# main.net
KiCad netlist of a schematic drawn in Altium Designer
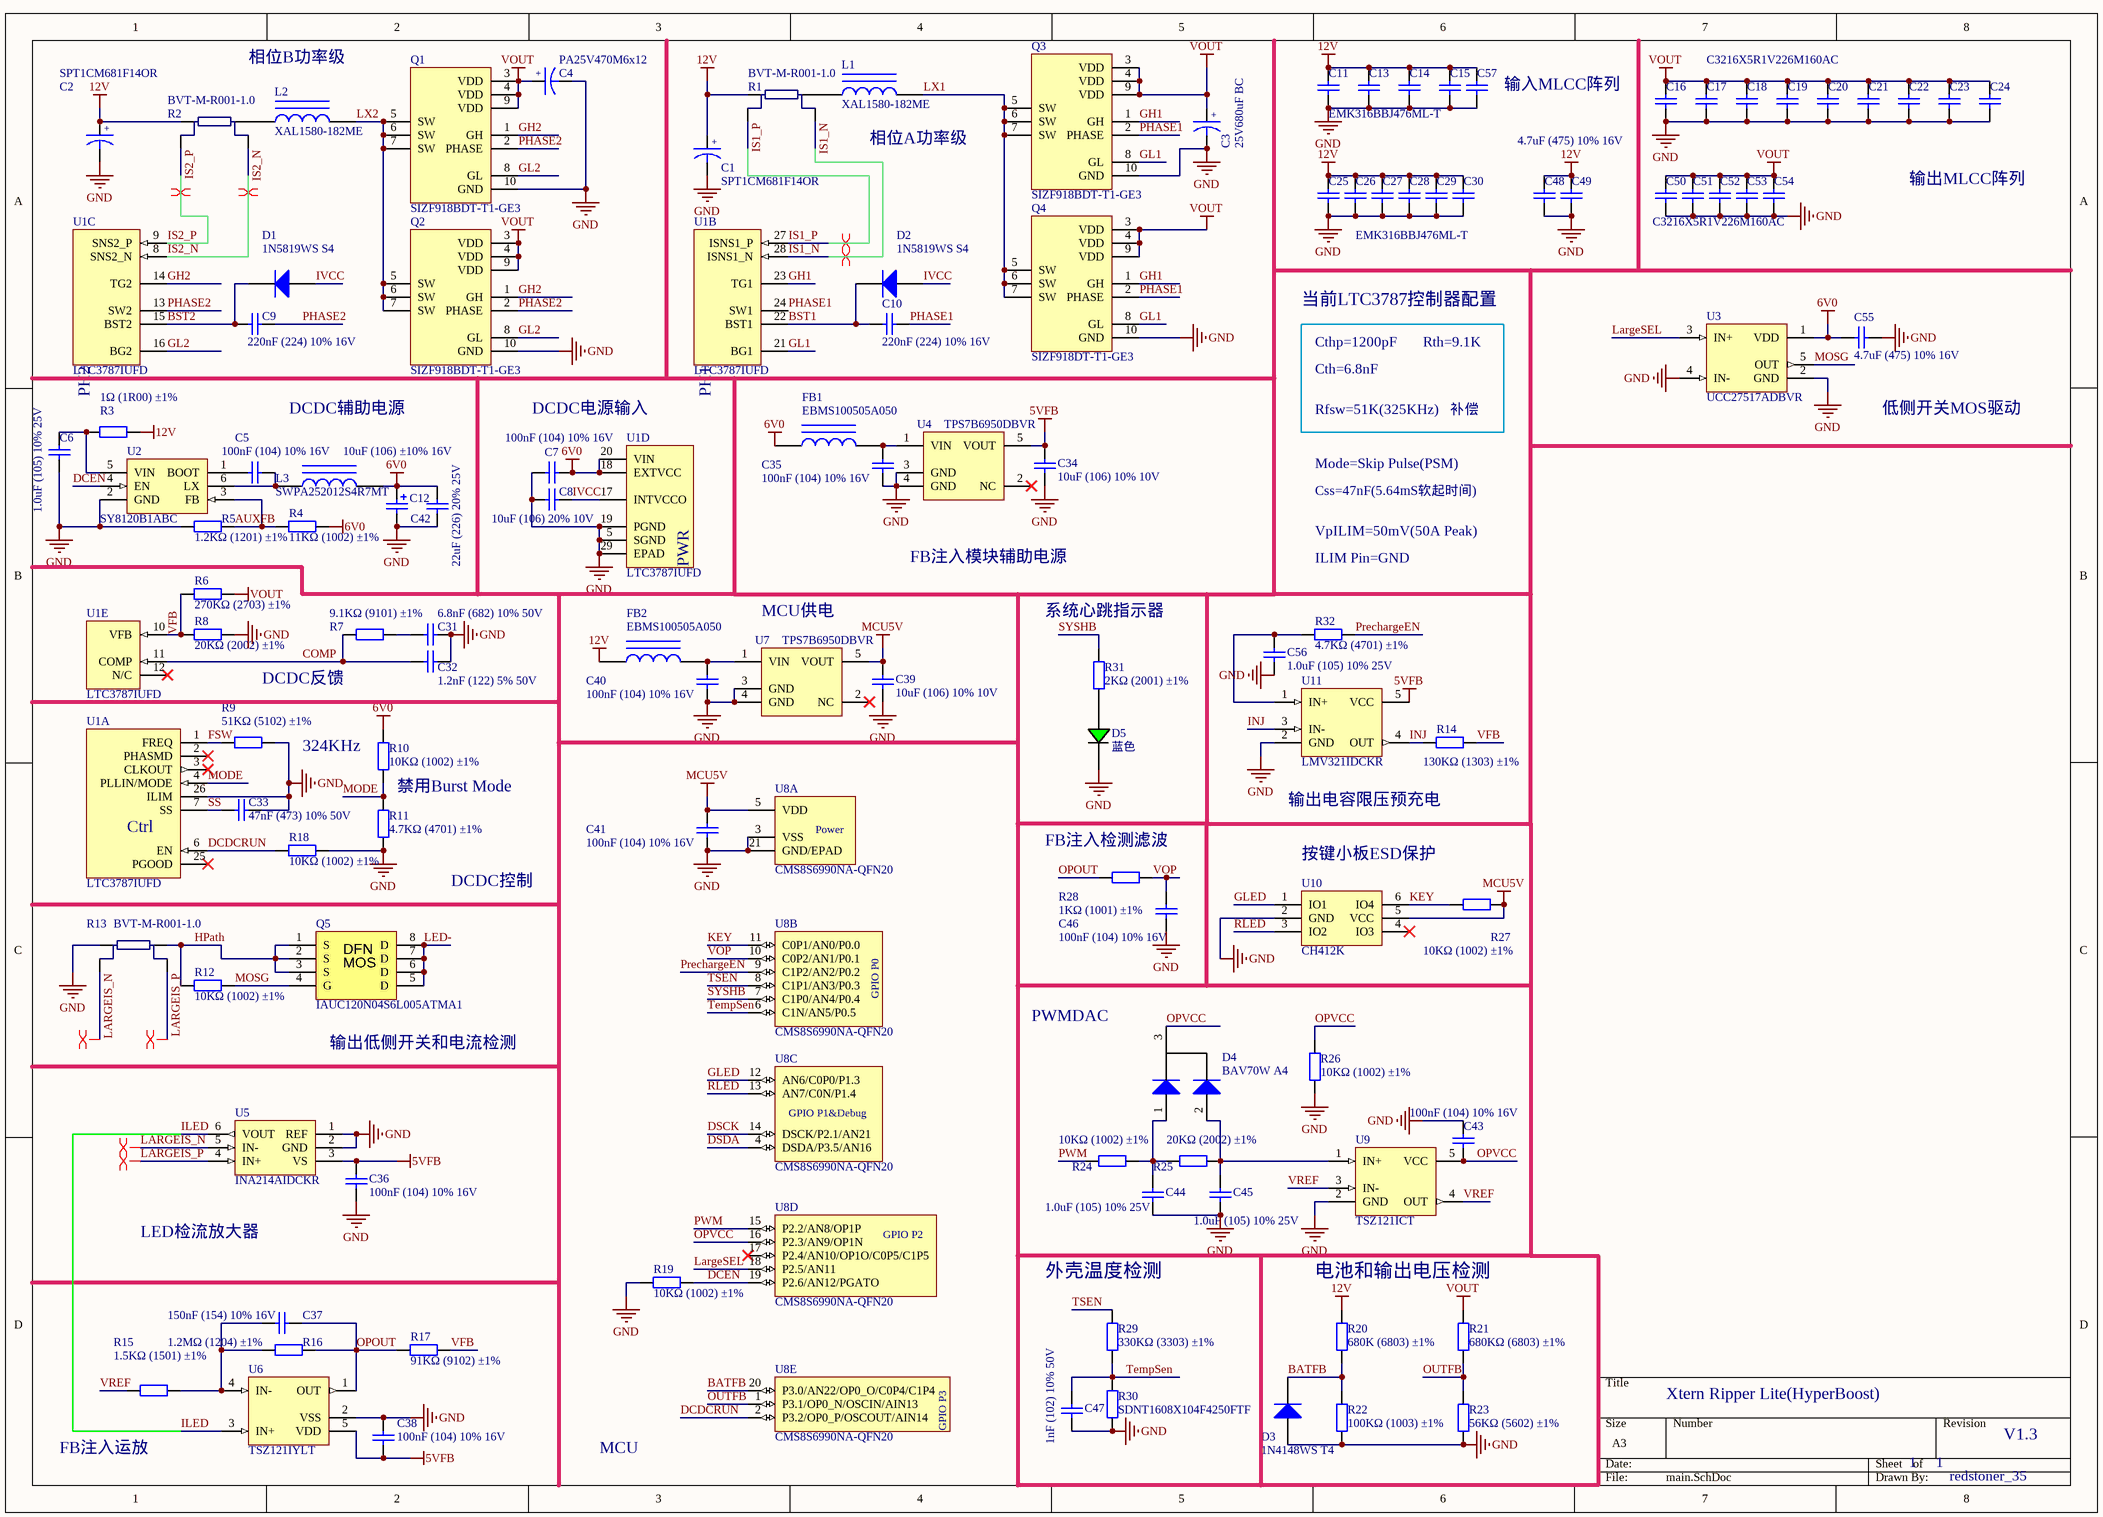
[diagram p0: main.SchDoc]

(export (version "E")
  (design (tool "Eeschema 10.0.6"))
  (components
    (comp (ref "C1")
      (value "SPT1CM681F14OR")
      (footprint "ElecCap_Hori")
      (description "直插固态电容，耐压16V容量680uF，尺寸6x11")
      (libsource (lib "山猫的集成库20190318") (part "CAP2"))
    )
    (comp (ref "C2")
      (value "SPT1CM681F14OR")
      (footprint "ElecCap_Hori")
      (description "直插固态电容，耐压16V容量680uF，尺寸6x11")
      (libsource (lib "山猫的集成库20190318") (part "CAP2"))
    )
    (comp (ref "C3")
      (value "25V680uF BC")
      (footprint "ElecCap_Hori")
      (description "绿宝石直插固态电容 680uF 25V BC系列，体积6x15")
      (libsource (lib "山猫的集成库20190318") (part "CAP2"))
    )
    (comp (ref "C4")
      (value "PA25V470M6x12")
      (footprint "ElecCap_Hori")
      (description "105°C 2000Hrs 直插固态电容。耐压25V容量470uF，尺寸D6.3mmxL12mm")
      (libsource (lib "山猫的集成库20190318") (part "CAP2"))
    )
    (comp (ref "C5")
      (value "100nF (104) 10% 16V")
      (footprint "0402_C")
      (description "贴片电容")
      (libsource (lib "Miscellaneous Devices LC") (part "0402 100nF (104) 10% 16V"))
    )
    (comp (ref "C6")
      (value "1.0uF (105) 10% 25V")
      (footprint "0402_C")
      (description "贴片电容")
      (libsource (lib "Miscellaneous Devices LC") (part "0402 1.0uF (105) 10% 25V"))
    )
    (comp (ref "C7")
      (value "100nF (104) 10% 16V")
      (footprint "0402_C")
      (description "贴片电容")
      (libsource (lib "Miscellaneous Devices LC") (part "0402 100nF (104) 10% 16V"))
    )
    (comp (ref "C8")
      (value "10uF (106) 20% 10V")
      (footprint "0402_C")
      (description "贴片电容")
      (libsource (lib "Miscellaneous Devices LC") (part "0402 10uF (106) 20% 6.3V"))
    )
    (comp (ref "C9")
      (value "220nF (224) 10% 16V")
      (footprint "0402_C")
      (description "贴片电容")
      (libsource (lib "Miscellaneous Devices LC") (part "0402 220nF (224) 10% 16V"))
    )
    (comp (ref "C10")
      (value "220nF (224) 10% 16V")
      (footprint "0402_C")
      (description "贴片电容")
      (libsource (lib "Miscellaneous Devices LC") (part "0402 220nF (224) 10% 16V"))
    )
    (comp (ref "C11")
      (value "EMK316BBJ476ML-T")
      (footprint "1206C")
      (description "1206尺寸太诱MLCC 16V 47uF X5R ±20%")
      (libsource (lib "山猫的集成库20190318") (part "Cap"))
    )
    (comp (ref "C12")
      (value "10uF (106) ±10% 16V")
      (footprint "CASE-A_3216")
      (description "钽电容")
      (libsource (lib "Miscellaneous Devices LC") (part "3216 10uF (106) 10% 16V"))
    )
    (comp (ref "C13")
      (value "EMK316BBJ476ML-T")
      (footprint "1206C")
      (description "1206尺寸太诱MLCC 16V 47uF X5R ±20%")
      (libsource (lib "山猫的集成库20190318") (part "Cap"))
    )
    (comp (ref "C14")
      (value "EMK316BBJ476ML-T")
      (footprint "1206C")
      (description "1206尺寸太诱MLCC 16V 47uF X5R ±20%")
      (libsource (lib "山猫的集成库20190318") (part "Cap"))
    )
    (comp (ref "C15")
      (value "EMK316BBJ476ML-T")
      (footprint "1206C")
      (description "1206尺寸太诱MLCC 16V 47uF X5R ±20%")
      (libsource (lib "山猫的集成库20190318") (part "Cap"))
    )
    (comp (ref "C16")
      (value "C3216X5R1V226M160AC")
      (footprint "1206C")
      (description "1206尺寸TDK MLCC 35V 22uF")
      (libsource (lib "山猫的集成库20190318") (part "Cap"))
    )
    (comp (ref "C17")
      (value "C3216X5R1V226M160AC")
      (footprint "1206C")
      (description "1206尺寸TDK MLCC 35V 22uF")
      (libsource (lib "山猫的集成库20190318") (part "Cap"))
    )
    (comp (ref "C18")
      (value "C3216X5R1V226M160AC")
      (footprint "1206C")
      (description "1206尺寸TDK MLCC 35V 22uF")
      (libsource (lib "山猫的集成库20190318") (part "Cap"))
    )
    (comp (ref "C19")
      (value "C3216X5R1V226M160AC")
      (footprint "1206C")
      (description "1206尺寸TDK MLCC 35V 22uF")
      (libsource (lib "山猫的集成库20190318") (part "Cap"))
    )
    (comp (ref "C20")
      (value "C3216X5R1V226M160AC")
      (footprint "1206C")
      (description "1206尺寸TDK MLCC 35V 22uF")
      (libsource (lib "山猫的集成库20190318") (part "Cap"))
    )
    (comp (ref "C21")
      (value "C3216X5R1V226M160AC")
      (footprint "1206C")
      (description "1206尺寸TDK MLCC 35V 22uF")
      (libsource (lib "山猫的集成库20190318") (part "Cap"))
    )
    (comp (ref "C22")
      (value "C3216X5R1V226M160AC")
      (footprint "1206C")
      (description "1206尺寸TDK MLCC 35V 22uF")
      (libsource (lib "山猫的集成库20190318") (part "Cap"))
    )
    (comp (ref "C23")
      (value "C3216X5R1V226M160AC")
      (footprint "1206C")
      (description "1206尺寸TDK MLCC 35V 22uF")
      (libsource (lib "山猫的集成库20190318") (part "Cap"))
    )
    (comp (ref "C24")
      (value "C3216X5R1V226M160AC")
      (footprint "1206C")
      (description "1206尺寸TDK MLCC 35V 22uF")
      (libsource (lib "山猫的集成库20190318") (part "Cap"))
    )
    (comp (ref "C25")
      (value "EMK316BBJ476ML-T")
      (footprint "1206C")
      (description "1206尺寸太诱MLCC 16V 47uF X5R ±20%")
      (libsource (lib "山猫的集成库20190318") (part "Cap"))
    )
    (comp (ref "C26")
      (value "EMK316BBJ476ML-T")
      (footprint "1206C")
      (description "1206尺寸太诱MLCC 16V 47uF X5R ±20%")
      (libsource (lib "山猫的集成库20190318") (part "Cap"))
    )
    (comp (ref "C27")
      (value "EMK316BBJ476ML-T")
      (footprint "1206C")
      (description "1206尺寸太诱MLCC 16V 47uF X5R ±20%")
      (libsource (lib "山猫的集成库20190318") (part "Cap"))
    )
    (comp (ref "C28")
      (value "EMK316BBJ476ML-T")
      (footprint "1206C")
      (description "1206尺寸太诱MLCC 16V 47uF X5R ±20%")
      (libsource (lib "山猫的集成库20190318") (part "Cap"))
    )
    (comp (ref "C29")
      (value "EMK316BBJ476ML-T")
      (footprint "1206C")
      (description "1206尺寸太诱MLCC 16V 47uF X5R ±20%")
      (libsource (lib "山猫的集成库20190318") (part "Cap"))
    )
    (comp (ref "C30")
      (value "EMK316BBJ476ML-T")
      (footprint "1206C")
      (description "1206尺寸太诱MLCC 16V 47uF X5R ±20%")
      (libsource (lib "山猫的集成库20190318") (part "Cap"))
    )
    (comp (ref "C31")
      (value "6.8nF (682) 10% 50V")
      (footprint "0402_C")
      (description "贴片电容")
      (libsource (lib "Miscellaneous Devices LC") (part "0402 6.8nF (682) 10% 50V"))
    )
    (comp (ref "C32")
      (value "1.2nF (122) 5% 50V")
      (footprint "0402_C")
      (description "贴片电容")
      (libsource (lib "Miscellaneous Devices LC") (part "0402 100pF (101) 5% 50V"))
    )
    (comp (ref "C33")
      (value "47nF (473) 10% 50V")
      (footprint "0402_C")
      (description "贴片电容")
      (libsource (lib "Miscellaneous Devices LC") (part "0402 100nF (104) 10% 16V"))
    )
    (comp (ref "C34")
      (value "10uF (106) 10% 10V")
      (footprint "0603_C")
      (description "贴片电容")
      (libsource (lib "Miscellaneous Devices LC") (part "0603 10uF (106) 10% 10V"))
    )
    (comp (ref "C35")
      (value "100nF (104) 10% 16V")
      (footprint "0402_C")
      (description "贴片电容")
      (libsource (lib "Miscellaneous Devices LC") (part "0402 100nF (104) 10% 16V"))
    )
    (comp (ref "C36")
      (value "100nF (104) 10% 16V")
      (footprint "0402_C")
      (description "贴片电容")
      (libsource (lib "Miscellaneous Devices LC") (part "0402 100nF (104) 10% 16V"))
    )
    (comp (ref "C37")
      (value "150nF (154) 10% 16V")
      (footprint "0402_C")
      (description "贴片电容")
      (libsource (lib "Miscellaneous Devices LC") (part "0402 100nF (104) 10% 16V"))
    )
    (comp (ref "C38")
      (value "100nF (104) 10% 16V")
      (footprint "0402_C")
      (description "贴片电容")
      (libsource (lib "Miscellaneous Devices LC") (part "0402 100nF (104) 10% 16V"))
    )
    (comp (ref "C39")
      (value "10uF (106) 10% 10V")
      (footprint "0603_C")
      (description "贴片电容")
      (libsource (lib "Miscellaneous Devices LC") (part "0603 10uF (106) 10% 10V"))
    )
    (comp (ref "C40")
      (value "100nF (104) 10% 16V")
      (footprint "0402_C")
      (description "贴片电容")
      (libsource (lib "Miscellaneous Devices LC") (part "0402 100nF (104) 10% 16V"))
    )
    (comp (ref "C41")
      (value "100nF (104) 10% 16V")
      (footprint "0402_C")
      (description "贴片电容")
      (libsource (lib "Miscellaneous Devices LC") (part "0402 100nF (104) 10% 16V"))
    )
    (comp (ref "C42")
      (value "22uF (226) 20% 25V")
      (footprint "0805_C")
      (description "贴片电容")
      (libsource (lib "Miscellaneous Devices LC") (part "0805 22uF (226) 20% 25V"))
    )
    (comp (ref "C43")
      (value "100nF (104) 10% 16V")
      (footprint "0402_C")
      (description "贴片电容")
      (libsource (lib "Miscellaneous Devices LC") (part "0402 100nF (104) 10% 16V"))
    )
    (comp (ref "C44")
      (value "1.0uF (105) 10% 25V")
      (footprint "0402_C")
      (description "贴片电容")
      (libsource (lib "Miscellaneous Devices LC") (part "0402 1.0uF (105) 10% 25V"))
    )
    (comp (ref "C45")
      (value "1.0uF (105) 10% 25V")
      (footprint "0402_C")
      (description "贴片电容")
      (libsource (lib "Miscellaneous Devices LC") (part "0402 1.0uF (105) 10% 25V"))
    )
    (comp (ref "C46")
      (value "100nF (104) 10% 16V")
      (footprint "0402_C")
      (description "贴片电容")
      (libsource (lib "Miscellaneous Devices LC") (part "0402 100nF (104) 10% 16V"))
    )
    (comp (ref "C47")
      (value "1nF (102) 10% 50V")
      (footprint "0402_C")
      (description "贴片电容")
      (libsource (lib "Miscellaneous Devices LC") (part "0402 1nF (102) 10% 50V"))
    )
    (comp (ref "C48")
      (value "4.7uF (475) 10% 16V")
      (footprint "0603_C")
      (description "贴片电容")
      (libsource (lib "Miscellaneous Devices LC") (part "0603 4.7uF (475) 10% 16V"))
    )
    (comp (ref "C49")
      (value "4.7uF (475) 10% 16V")
      (footprint "0603_C")
      (description "贴片电容")
      (libsource (lib "Miscellaneous Devices LC") (part "0603 4.7uF (475) 10% 16V"))
    )
    (comp (ref "C50")
      (value "C3216X5R1V226M160AC")
      (footprint "1206C")
      (description "1206尺寸TDK MLCC 35V 22uF")
      (libsource (lib "山猫的集成库20190318") (part "Cap"))
    )
    (comp (ref "C51")
      (value "C3216X5R1V226M160AC")
      (footprint "1206C")
      (description "1206尺寸TDK MLCC 35V 22uF")
      (libsource (lib "山猫的集成库20190318") (part "Cap"))
    )
    (comp (ref "C52")
      (value "C3216X5R1V226M160AC")
      (footprint "1206C")
      (description "1206尺寸TDK MLCC 35V 22uF")
      (libsource (lib "山猫的集成库20190318") (part "Cap"))
    )
    (comp (ref "C53")
      (value "C3216X5R1V226M160AC")
      (footprint "1206C")
      (description "1206尺寸TDK MLCC 35V 22uF")
      (libsource (lib "山猫的集成库20190318") (part "Cap"))
    )
    (comp (ref "C54")
      (value "C3216X5R1V226M160AC")
      (footprint "1206C")
      (description "1206尺寸TDK MLCC 35V 22uF")
      (libsource (lib "山猫的集成库20190318") (part "Cap"))
    )
    (comp (ref "C55")
      (value "4.7uF (475) 10% 16V")
      (footprint "0603_C")
      (description "贴片电容")
      (libsource (lib "Miscellaneous Devices LC") (part "0603 4.7uF (475) 10% 16V"))
    )
    (comp (ref "C56")
      (value "1.0uF (105) 10% 25V")
      (footprint "0402_C")
      (description "贴片电容")
      (libsource (lib "Miscellaneous Devices LC") (part "0402 1.0uF (105) 10% 25V"))
    )
    (comp (ref "C57")
      (value "EMK316BBJ476ML-T")
      (footprint "1206C")
      (description "1206尺寸太诱MLCC 16V 47uF X5R ±20%")
      (libsource (lib "山猫的集成库20190318") (part "Cap"))
    )
    (comp (ref "D1")
      (value "1N5819WS S4")
      (footprint "SOD-323")
      (description "二极管")
      (libsource (lib "Miscellaneous Devices LC") (part "SOD-323 1N4148WS T4"))
    )
    (comp (ref "D2")
      (value "1N5819WS S4")
      (footprint "SOD-323")
      (description "二极管")
      (libsource (lib "Miscellaneous Devices LC") (part "SOD-323 1N4148WS T4"))
    )
    (comp (ref "D3")
      (value "1N4148WS T4")
      (footprint "SOD-323")
      (description "二极管")
      (libsource (lib "Miscellaneous Devices LC") (part "SOD-323 1N4148WS T4"))
    )
    (comp (ref "D4")
      (value "BAV70W A4")
      (footprint "SC70-3")
      (description "开关二极管")
      (libsource (lib "Miscellaneous Devices LC") (part "SOT-23 BAV70 A4"))
    )
    (comp (ref "D5")
      (value "蓝色")
      (footprint "LED-0402")
      (description "0402(1005)贴片发光二极管")
      (libsource (lib "custom") (part "LED0402"))
    )
    (comp (ref "FB1")
      (value "EBMS100505A050")
      (footprint "0402_L")
      (description "贴片磁珠 200mA 5R±25% 100MHz")
      (libsource (lib "Miscellaneous Devices LC") (part "0402 12nH  5%"))
    )
    (comp (ref "FB2")
      (value "EBMS100505A050")
      (footprint "0402_L")
      (description "贴片磁珠 200mA 5R±25% 100MHz")
      (libsource (lib "Miscellaneous Devices LC") (part "0402 12nH  5%"))
    )
    (comp (ref "L1")
      (value "XAL1580-182ME")
      (footprint "XAL1580_xxxME")
      (description "线艺XAL系列电感")
      (libsource (lib "Miscellaneous Devices") (part "Inductor Iron"))
    )
    (comp (ref "L2")
      (value "XAL1580-182ME")
      (footprint "XAL1580_xxxME")
      (description "线艺XAL系列电感")
      (libsource (lib "Miscellaneous Devices") (part "Inductor Iron"))
    )
    (comp (ref "L3")
      (value "SWPA252012S4R7MT")
      (footprint "SWPA252010S")
      (description "线绕功率电感 2.5x2.0mm尺寸 1.2mm高度")
      (libsource (lib "") (part "Inductor Iron_1"))
    )
    (comp (ref "Q1")
      (value "SIZF918BDT-T1-GE3")
      (footprint "AOE6936")
      (description "30V Dual N-Channel 30 V (D-S) MOSFET With Schottky Diodes 3.6/1.5mΩ RdsON")
      (libsource (lib "custom") (part "AOE6936"))
    )
    (comp (ref "Q2")
      (value "SIZF918BDT-T1-GE3")
      (footprint "AOE6936")
      (description "30V Dual N-Channel 30 V (D-S) MOSFET With Schottky Diodes 3.6/1.5mΩ RdsON")
      (libsource (lib "custom") (part "AOE6936"))
    )
    (comp (ref "Q3")
      (value "SIZF918BDT-T1-GE3")
      (footprint "AOE6936")
      (description "30V Dual N-Channel 30 V (D-S) MOSFET With Schottky Diodes 3.6/1.5mΩ RdsON")
      (libsource (lib "custom") (part "AOE6936"))
    )
    (comp (ref "Q4")
      (value "SIZF918DT-T1-GE3")
      (footprint "AOE6936")
      (description "30V Dual N-Channel 30 V (D-S) MOSFET With Schottky Diodes 3.6/1.5mΩ RdsON")
      (libsource (lib "custom") (part "AOE6936"))
    )
    (comp (ref "Q5")
      (value "IAUC120N04S6L005ATMA1")
      (footprint "SON/DFN5x6(MOS)")
      (description "0.5mΩ 120A 40V OptiMOS 6 车规级MOSFET")
      (libsource (lib "custom") (part "SON/DFN5x6 MOS"))
    )
    (comp (ref "R1")
      (value "BVT-M-R001-1.0")
      (footprint "2512-Virtual4Wire")
      (description "德国伊萨精密检流电阻，2512 1mΩ±1% 锰铜材质 <50ppm/K P70℃=3W")
      (libsource (lib "custom") (part "shunt"))
    )
    (comp (ref "R2")
      (value "BVT-M-R001-1.0")
      (footprint "2512-Virtual4Wire")
      (description "德国伊萨精密检流电阻，2512 1mΩ±1% 锰铜材质 <50ppm/K P70℃=3W")
      (libsource (lib "custom") (part "shunt"))
    )
    (comp (ref "R3")
      (value "1Ω (1R00) ±1%")
      (footprint "0402_R")
      (description "贴片电阻")
      (libsource (lib "Miscellaneous Devices LC") (part "0402 1Ω (1R00) 1%"))
    )
    (comp (ref "R4")
      (value "11KΩ (1002) ±1%")
      (footprint "0402_R")
      (description "贴片电阻")
      (libsource (lib "") (part "0402 10KΩ (1002) 1%_2"))
    )
    (comp (ref "R5")
      (value "1.2KΩ (1201) ±1%")
      (footprint "0402_R")
      (description "贴片电阻")
      (libsource (lib "") (part "0402 10KΩ (1002) 1%_2"))
    )
    (comp (ref "R6")
      (value "270KΩ (2703) ±1%")
      (footprint "0402_R")
      (description "贴片电阻")
      (libsource (lib "") (part "0402 100KΩ (1003) 1%_1"))
    )
    (comp (ref "R7")
      (value "9.1KΩ (9101) ±1%")
      (footprint "0402_R")
      (description "贴片电阻")
      (libsource (lib "Miscellaneous Devices LC") (part "0402 10KΩ (1002) 1%"))
    )
    (comp (ref "R8")
      (value "20KΩ (2002) ±1%")
      (footprint "0402_R")
      (description "贴片电阻")
      (libsource (lib "Miscellaneous Devices LC") (part "0402 18KΩ (1802) 1%"))
    )
    (comp (ref "R9")
      (value "51KΩ (5102) ±1%")
      (footprint "0402_R")
      (description "贴片电阻")
      (libsource (lib "Miscellaneous Devices LC") (part "0402 56KΩ (5602) 1%"))
    )
    (comp (ref "R10")
      (value "10KΩ (1002) ±1%")
      (footprint "0402_R")
      (description "贴片电阻")
      (libsource (lib "") (part "0402 10KΩ (1002) 1%_1"))
    )
    (comp (ref "R11")
      (value "4.7KΩ (4701) ±1%")
      (footprint "0402_R")
      (description "贴片电阻")
      (libsource (lib "Miscellaneous Devices LC") (part "0402 4.7KΩ (4701) 1%"))
    )
    (comp (ref "R12")
      (value "10KΩ (1002) ±1%")
      (footprint "0402_R")
      (description "贴片电阻")
      (libsource (lib "") (part "0402 10KΩ (1002) 1%_2"))
    )
    (comp (ref "R13")
      (value "BVT-M-R001-1.0")
      (footprint "2512-Virtual4Wire")
      (description "德国伊萨精密检流电阻，2512 1mΩ±1% 锰铜材质 <50ppm/K P70℃=3W")
      (libsource (lib "custom") (part "shunt"))
    )
    (comp (ref "R14")
      (value "130KΩ (1303) ±1%")
      (footprint "0402_R")
      (description "贴片电阻")
      (libsource (lib "") (part "0402 100KΩ (1003) 1%_1"))
    )
    (comp (ref "R15")
      (value "1.5KΩ (1501) ±1%")
      (footprint "0402_R")
      (description "贴片电阻")
      (libsource (lib "Miscellaneous Devices LC") (part "0402 470Ω (4700) 1%"))
    )
    (comp (ref "R16")
      (value "1.2MΩ (1204) ±1%")
      (footprint "0402_R")
      (description "贴片电阻")
      (libsource (lib "Miscellaneous Devices LC") (part "0402 1MΩ (1004) 1%"))
    )
    (comp (ref "R17")
      (value "91KΩ (9102) ±1%")
      (footprint "0402_R")
      (description "贴片电阻")
      (libsource (lib "") (part "0402 100KΩ (1003) 1%_1"))
    )
    (comp (ref "R18")
      (value "10KΩ (1002) ±1%")
      (footprint "0402_R")
      (description "贴片电阻")
      (libsource (lib "Miscellaneous Devices LC") (part "0402 10KΩ (1002) 1%"))
    )
    (comp (ref "R19")
      (value "10KΩ (1002) ±1%")
      (footprint "0402_R")
      (description "贴片电阻")
      (libsource (lib "Miscellaneous Devices LC") (part "0402 10KΩ (1002) 1%"))
    )
    (comp (ref "R20")
      (value "680K (6803) ±1%")
      (footprint "0402_R")
      (description "贴片电阻")
      (libsource (lib "Miscellaneous Devices LC") (part "0402 680Ω (6800) 1%"))
    )
    (comp (ref "R21")
      (value "680KΩ (6803) ±1%")
      (footprint "0402_R")
      (description "贴片电阻")
      (libsource (lib "Miscellaneous Devices LC") (part "0402 470KΩ (4703) 1%"))
    )
    (comp (ref "R22")
      (value "100KΩ (1003) ±1%")
      (footprint "0402_R")
      (description "贴片电阻")
      (libsource (lib "Miscellaneous Devices LC") (part "0402 100KΩ (1003) 1%"))
    )
    (comp (ref "R23")
      (value "56KΩ (5602) ±1%")
      (footprint "0402_R")
      (description "贴片电阻")
      (libsource (lib "Miscellaneous Devices LC") (part "0402 100KΩ (1003) 1%"))
    )
    (comp (ref "R24")
      (value "10KΩ (1002) ±1%")
      (footprint "0402_R")
      (description "贴片电阻")
      (libsource (lib "Miscellaneous Devices LC") (part "0402 10KΩ (1002) 1%"))
    )
    (comp (ref "R25")
      (value "20KΩ (2002) ±1%")
      (footprint "0402_R")
      (description "贴片电阻")
      (libsource (lib "Miscellaneous Devices LC") (part "0402 20KΩ (2002) 1%"))
    )
    (comp (ref "R26")
      (value "10KΩ (1002) ±1%")
      (footprint "0402_R")
      (description "贴片电阻")
      (libsource (lib "") (part "0402 10KΩ (1002) 1%_1"))
    )
    (comp (ref "R27")
      (value "10KΩ (1002) ±1%")
      (footprint "0402_R")
      (description "贴片电阻")
      (libsource (lib "Miscellaneous Devices LC") (part "0402 10KΩ (1002) 1%"))
    )
    (comp (ref "R28")
      (value "1KΩ (1001) ±1%")
      (footprint "0402_R")
      (description "贴片电阻")
      (libsource (lib "Miscellaneous Devices LC") (part "0402 1KΩ (1001) 1%"))
    )
    (comp (ref "R29")
      (value "330KΩ (3303) ±1%")
      (footprint "0402_R")
      (description "贴片电阻")
      (libsource (lib "Miscellaneous Devices LC") (part "0402 330KΩ (3303) 1%"))
    )
    (comp (ref "R30")
      (value "SDNT1608X104F4250FTF")
      (footprint "0603_R")
      (description "0603贴片NTC热敏电阻，100KΩ (1003) ±1% B4250")
      (libsource (lib "Miscellaneous Devices LC") (part "0603 100KΩ (1003) 1%"))
    )
    (comp (ref "R31")
      (value "2KΩ (2001) ±1%")
      (footprint "0402_R")
      (description "贴片电阻")
      (libsource (lib "Miscellaneous Devices LC") (part "0402 2KΩ (2001) 1%"))
    )
    (comp (ref "R32")
      (value "4.7KΩ (4701) ±1%")
      (footprint "0402_R")
      (description "贴片电阻")
      (libsource (lib "Miscellaneous Devices LC") (part "0402 20KΩ (2002) 1%"))
    )
    (comp (ref "U1")
      (value "LTC3787IUFD")
      (footprint "UFD-QFN28")
      (description "PolyPhase Synchronous Boost Controller for 2 Phases")
      (libsource (lib "custom") (part "LTC3787IUFD"))
    )
    (comp (ref "U2")
      (value "SY8120B1ABC")
      (footprint "SOT95P245X110-6N")
      (description "2A输出电流，18V耐压同步降压转换器，SOT-23-6封装")
      (libsource (lib "custom") (part "SY8120"))
    )
    (comp (ref "U3")
      (value "UCC27517ADBVR")
      (footprint "SOT95P245X110-5N")
      (description "4A Gate Driver SOT-23 Low side")
      (libsource (lib "custom") (part "UCC27517ADBVR"))
    )
    (comp (ref "U4")
      (value "TPS7B6950DBVR")
      (footprint "SOT95P245X110-5N")
      (description "150mA 40V max input Ultra low Iq LDO,fixed 5V output")
      (libsource (lib "custom") (part "TPS7B6933DBVR"))
    )
    (comp (ref "U5")
      (value "INA214AIDCKR")
      (footprint "SC70-6")
      (description "100V/V增益 26V最高共模电压，高低测通用双向高精度检流放大器 SC70-6封装")
      (libsource (lib "custom") (part "INA199A2DCKR"))
    )
    (comp (ref "U6")
      (value "TSZ121IYLT")
      (footprint "SOT95P245X110-5N")
      (description "高精度零漂移低功耗5V运放 400Khz GBW SOT23-5封装")
      (libsource (lib "custom") (part "TLV333IDBVR"))
    )
    (comp (ref "U7")
      (value "TPS7B6950DBVR")
      (footprint "SOT95P245X110-5N")
      (description "150mA 40V max input Ultra low Iq LDO,fixed 5V output")
      (libsource (lib "custom") (part "TPS7B6933DBVR"))
    )
    (comp (ref "U8")
      (value "CMS8S6990NA-QFN20")
      (footprint "QFN40P300X300X800_HS-21N")
      (description "增强型闪存1T 8051单片机，16KB Flash 256+1K XRAM")
      (libsource (lib "custom") (part "CM8S6990NA-QFN20"))
    )
    (comp (ref "U9")
      (value "TSZ121ICT")
      (footprint "SC70-5")
      (description "高精度零漂移低功耗5V运放 400Khz GBW SC70-5封装")
      (libsource (lib "custom") (part "LMV321IDCKR"))
    )
    (comp (ref "U10")
      (value "CH412K")
      (footprint "SC70-6")
      (description "very low capacity quad IO ESD protection Array")
      (libsource (lib "custom") (part "CH412K"))
    )
    (comp (ref "U11")
      (value "LMV321IDCKR")
      (footprint "SC70-5")
      (description "CMOS超小型运算放大器，SC70-5")
      (libsource (lib "custom") (part "LMV321IDCKR"))
    )
  )
  (nets
    (net (code "1") (name "/AUXFB") (class "Default")
      (node (ref "R4") (pin "2") (pinfunction "2_2") (pintype "passive"))
      (node (ref "R5") (pin "1") (pinfunction "1_1") (pintype "passive"))
      (node (ref "U2") (pin "3") (pinfunction "FB_3") (pintype "input"))
    )
    (net (code "2") (name "/BATFB") (class "Default")
      (node (ref "D3") (pin "2") (pinfunction "K_2") (pintype "passive"))
      (node (ref "R20") (pin "1") (pinfunction "1_1") (pintype "passive"))
      (node (ref "R22") (pin "2") (pinfunction "2_2") (pintype "passive"))
      (node (ref "U8") (pin "20") (pinfunction "P3.0/AN22/OP0_O/C0P4/C1P4_20") (pintype "bidirectional"))
    )
    (net (code "3") (name "/BST1") (class "Default")
      (node (ref "C10") (pin "1") (pinfunction "1_1") (pintype "passive"))
      (node (ref "D2") (pin "2") (pinfunction "K_2") (pintype "passive"))
      (node (ref "U1") (pin "22") (pinfunction "BST1_22") (pintype "power_in"))
    )
    (net (code "4") (name "/BST2") (class "Default")
      (node (ref "C9") (pin "1") (pinfunction "1_1") (pintype "passive"))
      (node (ref "D1") (pin "2") (pinfunction "K_2") (pintype "passive"))
      (node (ref "U1") (pin "15") (pinfunction "BST2_15") (pintype "power_in"))
    )
    (net (code "5") (name "/COMP") (class "Default")
      (node (ref "C32") (pin "2") (pinfunction "2_2") (pintype "passive"))
      (node (ref "R7") (pin "1") (pinfunction "1_1") (pintype "passive"))
      (node (ref "U1") (pin "11") (pinfunction "COMP_11") (pintype "input"))
    )
    (net (code "6") (name "/DCDCRUN") (class "Default")
      (node (ref "R18") (pin "1") (pinfunction "1_1") (pintype "passive"))
      (node (ref "U1") (pin "6") (pinfunction "EN_6") (pintype "input"))
      (node (ref "U8") (pin "2") (pinfunction "P3.2/OP0_P/OSCOUT/AIN14_2") (pintype "bidirectional"))
    )
    (net (code "7") (name "/DCEN") (class "Default")
      (node (ref "R19") (pin "2") (pinfunction "2_2") (pintype "passive"))
      (node (ref "U2") (pin "4") (pinfunction "EN_4") (pintype "input"))
      (node (ref "U8") (pin "19") (pinfunction "P2.6/AN12/PGATO_19") (pintype "bidirectional"))
    )
    (net (code "8") (name "/DSCK") (class "Default")
      (node (ref "U8") (pin "14") (pinfunction "DSCK/P2.1/AN21_14") (pintype "bidirectional"))
    )
    (net (code "9") (name "/DSDA") (class "Default")
      (node (ref "U8") (pin "4") (pinfunction "DSDA/P3.5/AN16_4") (pintype "bidirectional"))
    )
    (net (code "10") (name "/FSW") (class "Default")
      (node (ref "R9") (pin "1") (pinfunction "1_1") (pintype "passive"))
      (node (ref "U1") (pin "1") (pinfunction "FREQ_1") (pintype "passive"))
    )
    (net (code "11") (name "/GH1") (class "Default")
      (node (ref "Q3") (pin "1") (pinfunction "GH_1") (pintype "passive"))
      (node (ref "Q4") (pin "1") (pinfunction "GH_1") (pintype "passive"))
      (node (ref "U1") (pin "23") (pinfunction "TG1_23") (pintype "power_in"))
    )
    (net (code "12") (name "/GH2") (class "Default")
      (node (ref "Q1") (pin "1") (pinfunction "GH_1") (pintype "passive"))
      (node (ref "Q2") (pin "1") (pinfunction "GH_1") (pintype "passive"))
      (node (ref "U1") (pin "14") (pinfunction "TG2_14") (pintype "power_in"))
    )
    (net (code "13") (name "/GL1") (class "Default")
      (node (ref "Q3") (pin "8") (pinfunction "GL_8") (pintype "passive"))
      (node (ref "Q4") (pin "8") (pinfunction "GL_8") (pintype "passive"))
      (node (ref "U1") (pin "21") (pinfunction "BG1_21") (pintype "power_in"))
    )
    (net (code "14") (name "/GL2") (class "Default")
      (node (ref "Q1") (pin "8") (pinfunction "GL_8") (pintype "passive"))
      (node (ref "Q2") (pin "8") (pinfunction "GL_8") (pintype "passive"))
      (node (ref "U1") (pin "16") (pinfunction "BG2_16") (pintype "power_in"))
    )
    (net (code "15") (name "/GLED") (class "Default")
      (node (ref "U10") (pin "1") (pinfunction "IO1_1") (pintype "passive"))
      (node (ref "U8") (pin "12") (pinfunction "AN6/C0P0/P1.3_12") (pintype "bidirectional"))
    )
    (net (code "16") (name "/HPath") (class "Default")
      (node (ref "Q5") (pin "1") (pinfunction "S_1") (pintype "passive"))
      (node (ref "Q5") (pin "2") (pinfunction "S_2") (pintype "passive"))
      (node (ref "Q5") (pin "3") (pinfunction "S_3") (pintype "passive"))
      (node (ref "R12") (pin "2") (pinfunction "2_2") (pintype "passive"))
      (node (ref "R13") (pin "1") (pinfunction "CIN_1") (pintype "passive"))
    )
    (net (code "17") (name "/ILED") (class "Default")
      (node (ref "U5") (pin "6") (pinfunction "VOUT_6") (pintype "output"))
      (node (ref "U6") (pin "3") (pinfunction "IN+_3") (pintype "input"))
    )
    (net (code "18") (name "/INJ") (class "Default")
      (node (ref "R14") (pin "1") (pinfunction "1_1") (pintype "passive"))
      (node (ref "U11") (pin "3") (pinfunction "IN-_3") (pintype "input"))
      (node (ref "U11") (pin "4") (pinfunction "OUT_4") (pintype "output"))
    )
    (net (code "19") (name "/IS1_N") (class "Default")
      (node (ref "R1") (pin "3") (pinfunction "CIN_3") (pintype "passive"))
      (node (ref "U1") (pin "28") (pinfunction "ISNS1_N_28") (pintype "input"))
    )
    (net (code "20") (name "/IS1_P") (class "Default")
      (node (ref "R1") (pin "2") (pinfunction "CIN_2") (pintype "passive"))
      (node (ref "U1") (pin "27") (pinfunction "ISNS1_P_27") (pintype "input"))
    )
    (net (code "21") (name "/IS2_N") (class "Default")
      (node (ref "R2") (pin "2") (pinfunction "CIN_2") (pintype "passive"))
      (node (ref "U1") (pin "8") (pinfunction "SNS2_N_8") (pintype "input"))
    )
    (net (code "22") (name "/IS2_P") (class "Default")
      (node (ref "R2") (pin "3") (pinfunction "CIN_3") (pintype "passive"))
      (node (ref "U1") (pin "9") (pinfunction "SNS2_P_9") (pintype "input"))
    )
    (net (code "23") (name "/IVCC") (class "Default")
      (node (ref "C8") (pin "2") (pinfunction "2_2") (pintype "passive"))
      (node (ref "D1") (pin "1") (pinfunction "A_1") (pintype "passive"))
      (node (ref "D2") (pin "1") (pinfunction "A_1") (pintype "passive"))
      (node (ref "U1") (pin "17") (pinfunction "INTVCCO_17") (pintype "power_in"))
    )
    (net (code "24") (name "/KEY") (class "Default")
      (node (ref "R27") (pin "1") (pinfunction "1_1") (pintype "passive"))
      (node (ref "U10") (pin "6") (pinfunction "IO4_6") (pintype "passive"))
      (node (ref "U8") (pin "11") (pinfunction "C0P1/AN0/P0.0_11") (pintype "bidirectional"))
    )
    (net (code "25") (name "/LARGEIS_N") (class "Default")
      (node (ref "R13") (pin "2") (pinfunction "CIN_2") (pintype "passive"))
      (node (ref "U5") (pin "5") (pinfunction "IN-_5") (pintype "input"))
    )
    (net (code "26") (name "/LARGEIS_P") (class "Default")
      (node (ref "R13") (pin "3") (pinfunction "CIN_3") (pintype "passive"))
      (node (ref "U5") (pin "4") (pinfunction "IN+_4") (pintype "input"))
    )
    (net (code "27") (name "/LED-") (class "Default")
      (node (ref "Q5") (pin "5") (pinfunction "D_5") (pintype "passive"))
      (node (ref "Q5") (pin "6") (pinfunction "D_6") (pintype "passive"))
      (node (ref "Q5") (pin "7") (pinfunction "D_7") (pintype "passive"))
      (node (ref "Q5") (pin "8") (pinfunction "D_8") (pintype "passive"))
    )
    (net (code "28") (name "/LX1") (class "Default")
      (node (ref "L1") (pin "2") (pinfunction "2_2") (pintype "passive"))
      (node (ref "Q3") (pin "5") (pinfunction "SW_5") (pintype "passive"))
      (node (ref "Q3") (pin "6") (pinfunction "SW_6") (pintype "passive"))
      (node (ref "Q3") (pin "7") (pinfunction "SW_7") (pintype "passive"))
      (node (ref "Q4") (pin "5") (pinfunction "SW_5") (pintype "passive"))
      (node (ref "Q4") (pin "6") (pinfunction "SW_6") (pintype "passive"))
      (node (ref "Q4") (pin "7") (pinfunction "SW_7") (pintype "passive"))
    )
    (net (code "29") (name "/LX2") (class "Default")
      (node (ref "L2") (pin "2") (pinfunction "2_2") (pintype "passive"))
      (node (ref "Q1") (pin "5") (pinfunction "SW_5") (pintype "passive"))
      (node (ref "Q1") (pin "6") (pinfunction "SW_6") (pintype "passive"))
      (node (ref "Q1") (pin "7") (pinfunction "SW_7") (pintype "passive"))
      (node (ref "Q2") (pin "5") (pinfunction "SW_5") (pintype "passive"))
      (node (ref "Q2") (pin "6") (pinfunction "SW_6") (pintype "passive"))
      (node (ref "Q2") (pin "7") (pinfunction "SW_7") (pintype "passive"))
    )
    (net (code "30") (name "/LargeSEL") (class "Default")
      (node (ref "U3") (pin "3") (pinfunction "IN+_3") (pintype "input"))
      (node (ref "U8") (pin "18") (pinfunction "P2.5/AN11_18") (pintype "bidirectional"))
    )
    (net (code "31") (name "/MODE") (class "Default")
      (node (ref "R10") (pin "1") (pinfunction "1_1") (pintype "passive"))
      (node (ref "R11") (pin "2") (pinfunction "2_2") (pintype "passive"))
      (node (ref "U1") (pin "4") (pinfunction "PLLIN/MODE_4") (pintype "input"))
    )
    (net (code "32") (name "/MOSG") (class "Default")
      (node (ref "Q5") (pin "4") (pinfunction "G_4") (pintype "passive"))
      (node (ref "R12") (pin "1") (pinfunction "1_1") (pintype "passive"))
      (node (ref "U3") (pin "5") (pinfunction "OUT_5") (pintype "output"))
    )
    (net (code "33") (name "/OPOUT") (class "Default")
      (node (ref "C37") (pin "2") (pinfunction "2_2") (pintype "passive"))
      (node (ref "R16") (pin "2") (pinfunction "2_2") (pintype "passive"))
      (node (ref "R17") (pin "1") (pinfunction "1_1") (pintype "passive"))
      (node (ref "R28") (pin "1") (pinfunction "1_1") (pintype "passive"))
      (node (ref "U6") (pin "1") (pinfunction "OUT_1") (pintype "output"))
    )
    (net (code "34") (name "/OPVCC") (class "Default")
      (node (ref "C43") (pin "2") (pinfunction "2_2") (pintype "passive"))
      (node (ref "D4") (pin "3") (pinfunction "K_3") (pintype "passive"))
      (node (ref "R26") (pin "2") (pinfunction "2_2") (pintype "passive"))
      (node (ref "U8") (pin "16") (pinfunction "P2.3/AN9/OP1N_16") (pintype "bidirectional"))
      (node (ref "U9") (pin "5") (pinfunction "VCC_5") (pintype "power_in"))
    )
    (net (code "35") (name "/OUTFB") (class "Default")
      (node (ref "R21") (pin "1") (pinfunction "1_1") (pintype "passive"))
      (node (ref "R23") (pin "2") (pinfunction "2_2") (pintype "passive"))
      (node (ref "U8") (pin "1") (pinfunction "P3.1/OP0_N/OSCIN/AIN13_1") (pintype "bidirectional"))
    )
    (net (code "36") (name "/PHASE1") (class "Default")
      (node (ref "C10") (pin "2") (pinfunction "2_2") (pintype "passive"))
      (node (ref "Q3") (pin "2") (pinfunction "PHASE_2") (pintype "passive"))
      (node (ref "Q4") (pin "2") (pinfunction "PHASE_2") (pintype "passive"))
      (node (ref "U1") (pin "24") (pinfunction "SW1_24") (pintype "power_in"))
    )
    (net (code "37") (name "/PHASE2") (class "Default")
      (node (ref "C9") (pin "2") (pinfunction "2_2") (pintype "passive"))
      (node (ref "Q1") (pin "2") (pinfunction "PHASE_2") (pintype "passive"))
      (node (ref "Q2") (pin "2") (pinfunction "PHASE_2") (pintype "passive"))
      (node (ref "U1") (pin "13") (pinfunction "SW2_13") (pintype "power_in"))
    )
    (net (code "38") (name "/PWM") (class "Default")
      (node (ref "R24") (pin "1") (pinfunction "1_1") (pintype "passive"))
      (node (ref "U8") (pin "15") (pinfunction "P2.2/AN8/OP1P_15") (pintype "bidirectional"))
    )
    (net (code "39") (name "/PrechargeEN") (class "Default")
      (node (ref "R32") (pin "2") (pinfunction "2_2") (pintype "passive"))
      (node (ref "U8") (pin "9") (pinfunction "C1P2/AN2/P0.2_9") (pintype "bidirectional"))
    )
    (net (code "40") (name "/RLED") (class "Default")
      (node (ref "U10") (pin "3") (pinfunction "IO2_3") (pintype "passive"))
      (node (ref "U8") (pin "13") (pinfunction "AN7/C0N/P1.4_13") (pintype "bidirectional"))
    )
    (net (code "41") (name "/SS") (class "Default")
      (node (ref "C33") (pin "1") (pinfunction "1_1") (pintype "passive"))
      (node (ref "U1") (pin "7") (pinfunction "SS_7") (pintype "passive"))
    )
    (net (code "42") (name "/SYSHB") (class "Default")
      (node (ref "R31") (pin "2") (pinfunction "2_2") (pintype "passive"))
      (node (ref "U8") (pin "7") (pinfunction "C1P0/AN4/P0.4_7") (pintype "bidirectional"))
    )
    (net (code "43") (name "/TSEN") (class "Default")
      (node (ref "R29") (pin "2") (pinfunction "2_2") (pintype "passive"))
      (node (ref "U8") (pin "8") (pinfunction "C1P1/AN3/P0.3_8") (pintype "bidirectional"))
    )
    (net (code "44") (name "/TempSen") (class "Default")
      (node (ref "C47") (pin "2") (pinfunction "2_2") (pintype "passive"))
      (node (ref "R29") (pin "1") (pinfunction "1_1") (pintype "passive"))
      (node (ref "R30") (pin "1") (pinfunction "1_1") (pintype "passive"))
      (node (ref "U8") (pin "6") (pinfunction "C1N/AN5/P0.5_6") (pintype "bidirectional"))
    )
    (net (code "45") (name "/VFB") (class "Default")
      (node (ref "R14") (pin "2") (pinfunction "2_2") (pintype "passive"))
      (node (ref "R17") (pin "2") (pinfunction "2_2") (pintype "passive"))
      (node (ref "R6") (pin "1") (pinfunction "1_1") (pintype "passive"))
      (node (ref "R8") (pin "1") (pinfunction "1_1") (pintype "passive"))
      (node (ref "U1") (pin "10") (pinfunction "VFB_10") (pintype "input"))
    )
    (net (code "46") (name "/VOP") (class "Default")
      (node (ref "C46") (pin "2") (pinfunction "2_2") (pintype "passive"))
      (node (ref "R28") (pin "2") (pinfunction "2_2") (pintype "passive"))
      (node (ref "U8") (pin "10") (pinfunction "C0P2/AN1/P0.1_10") (pintype "bidirectional"))
    )
    (net (code "47") (name "/VREF") (class "Default")
      (node (ref "R15") (pin "1") (pinfunction "1_1") (pintype "passive"))
      (node (ref "U9") (pin "3") (pinfunction "IN-_3") (pintype "input"))
      (node (ref "U9") (pin "4") (pinfunction "OUT_4") (pintype "output"))
    )
    (net (code "48") (name "5VFB") (class "Default")
      (node (ref "C34") (pin "2") (pinfunction "2_2") (pintype "passive"))
      (node (ref "C36") (pin "2") (pinfunction "2_2") (pintype "passive"))
      (node (ref "C38") (pin "1") (pinfunction "1_1") (pintype "passive"))
      (node (ref "U11") (pin "5") (pinfunction "VCC_5") (pintype "power_in"))
      (node (ref "U4") (pin "5") (pinfunction "VOUT_5") (pintype "power_in"))
      (node (ref "U5") (pin "3") (pinfunction "VS_3") (pintype "passive"))
      (node (ref "U6") (pin "5") (pinfunction "VDD_5") (pintype "power_in"))
    )
    (net (code "49") (name "6V0") (class "Default")
      (node (ref "C12") (pin "1") (pinfunction "1_1") (pintype "passive"))
      (node (ref "C42") (pin "2") (pinfunction "2_2") (pintype "passive"))
      (node (ref "C55") (pin "1") (pinfunction "1_1") (pintype "passive"))
      (node (ref "C7") (pin "2") (pinfunction "2_2") (pintype "passive"))
      (node (ref "FB1") (pin "1") (pinfunction "1_1") (pintype "passive"))
      (node (ref "L3") (pin "1") (pinfunction "1_1") (pintype "passive"))
      (node (ref "R10") (pin "2") (pinfunction "2_2") (pintype "passive"))
      (node (ref "R4") (pin "1") (pinfunction "1_1") (pintype "passive"))
      (node (ref "U1") (pin "18") (pinfunction "EXTVCC_18") (pintype "power_in"))
      (node (ref "U1") (pin "20") (pinfunction "VIN_20") (pintype "power_in"))
      (node (ref "U3") (pin "1") (pinfunction "VDD_1") (pintype "power_in"))
    )
    (net (code "50") (name "12V") (class "Default")
      (node (ref "C1") (pin "1") (pinfunction "1_1") (pintype "passive"))
      (node (ref "C11") (pin "2") (pinfunction "2_2") (pintype "passive"))
      (node (ref "C13") (pin "2") (pinfunction "2_2") (pintype "passive"))
      (node (ref "C14") (pin "2") (pinfunction "2_2") (pintype "passive"))
      (node (ref "C15") (pin "2") (pinfunction "2_2") (pintype "passive"))
      (node (ref "C2") (pin "1") (pinfunction "1_1") (pintype "passive"))
      (node (ref "C25") (pin "2") (pinfunction "2_2") (pintype "passive"))
      (node (ref "C26") (pin "2") (pinfunction "2_2") (pintype "passive"))
      (node (ref "C27") (pin "2") (pinfunction "2_2") (pintype "passive"))
      (node (ref "C28") (pin "2") (pinfunction "2_2") (pintype "passive"))
      (node (ref "C29") (pin "2") (pinfunction "2_2") (pintype "passive"))
      (node (ref "C30") (pin "2") (pinfunction "2_2") (pintype "passive"))
      (node (ref "C48") (pin "2") (pinfunction "2_2") (pintype "passive"))
      (node (ref "C49") (pin "2") (pinfunction "2_2") (pintype "passive"))
      (node (ref "C57") (pin "2") (pinfunction "2_2") (pintype "passive"))
      (node (ref "FB2") (pin "1") (pinfunction "1_1") (pintype "passive"))
      (node (ref "R1") (pin "0") (pinfunction "CIN_0") (pintype "passive"))
      (node (ref "R2") (pin "1") (pinfunction "CIN_1") (pintype "passive"))
      (node (ref "R20") (pin "2") (pinfunction "2_2") (pintype "passive"))
      (node (ref "R3") (pin "2") (pinfunction "2_2") (pintype "passive"))
    )
    (net (code "51") (name "GND") (class "Default")
      (node (ref "C1") (pin "2") (pinfunction "2_2") (pintype "passive"))
      (node (ref "C11") (pin "1") (pinfunction "1_1") (pintype "passive"))
      (node (ref "C12") (pin "2") (pinfunction "2_2") (pintype "passive"))
      (node (ref "C13") (pin "1") (pinfunction "1_1") (pintype "passive"))
      (node (ref "C14") (pin "1") (pinfunction "1_1") (pintype "passive"))
      (node (ref "C15") (pin "1") (pinfunction "1_1") (pintype "passive"))
      (node (ref "C16") (pin "1") (pinfunction "1_1") (pintype "passive"))
      (node (ref "C17") (pin "1") (pinfunction "1_1") (pintype "passive"))
      (node (ref "C18") (pin "1") (pinfunction "1_1") (pintype "passive"))
      (node (ref "C19") (pin "1") (pinfunction "1_1") (pintype "passive"))
      (node (ref "C2") (pin "2") (pinfunction "2_2") (pintype "passive"))
      (node (ref "C20") (pin "1") (pinfunction "1_1") (pintype "passive"))
      (node (ref "C21") (pin "1") (pinfunction "1_1") (pintype "passive"))
      (node (ref "C22") (pin "1") (pinfunction "1_1") (pintype "passive"))
      (node (ref "C23") (pin "1") (pinfunction "1_1") (pintype "passive"))
      (node (ref "C24") (pin "1") (pinfunction "1_1") (pintype "passive"))
      (node (ref "C25") (pin "1") (pinfunction "1_1") (pintype "passive"))
      (node (ref "C26") (pin "1") (pinfunction "1_1") (pintype "passive"))
      (node (ref "C27") (pin "1") (pinfunction "1_1") (pintype "passive"))
      (node (ref "C28") (pin "1") (pinfunction "1_1") (pintype "passive"))
      (node (ref "C29") (pin "1") (pinfunction "1_1") (pintype "passive"))
      (node (ref "C3") (pin "2") (pinfunction "2_2") (pintype "passive"))
      (node (ref "C30") (pin "1") (pinfunction "1_1") (pintype "passive"))
      (node (ref "C31") (pin "2") (pinfunction "2_2") (pintype "passive"))
      (node (ref "C32") (pin "1") (pinfunction "1_1") (pintype "passive"))
      (node (ref "C33") (pin "2") (pinfunction "2_2") (pintype "passive"))
      (node (ref "C34") (pin "1") (pinfunction "1_1") (pintype "passive"))
      (node (ref "C35") (pin "1") (pinfunction "1_1") (pintype "passive"))
      (node (ref "C36") (pin "1") (pinfunction "1_1") (pintype "passive"))
      (node (ref "C38") (pin "2") (pinfunction "2_2") (pintype "passive"))
      (node (ref "C39") (pin "1") (pinfunction "1_1") (pintype "passive"))
      (node (ref "C4") (pin "2") (pinfunction "2_2") (pintype "passive"))
      (node (ref "C40") (pin "1") (pinfunction "1_1") (pintype "passive"))
      (node (ref "C41") (pin "1") (pinfunction "1_1") (pintype "passive"))
      (node (ref "C42") (pin "1") (pinfunction "1_1") (pintype "passive"))
      (node (ref "C43") (pin "1") (pinfunction "1_1") (pintype "passive"))
      (node (ref "C44") (pin "1") (pinfunction "1_1") (pintype "passive"))
      (node (ref "C45") (pin "1") (pinfunction "1_1") (pintype "passive"))
      (node (ref "C46") (pin "1") (pinfunction "1_1") (pintype "passive"))
      (node (ref "C47") (pin "1") (pinfunction "1_1") (pintype "passive"))
      (node (ref "C48") (pin "1") (pinfunction "1_1") (pintype "passive"))
      (node (ref "C49") (pin "1") (pinfunction "1_1") (pintype "passive"))
      (node (ref "C50") (pin "1") (pinfunction "1_1") (pintype "passive"))
      (node (ref "C51") (pin "1") (pinfunction "1_1") (pintype "passive"))
      (node (ref "C52") (pin "1") (pinfunction "1_1") (pintype "passive"))
      (node (ref "C53") (pin "1") (pinfunction "1_1") (pintype "passive"))
      (node (ref "C54") (pin "1") (pinfunction "1_1") (pintype "passive"))
      (node (ref "C55") (pin "2") (pinfunction "2_2") (pintype "passive"))
      (node (ref "C56") (pin "1") (pinfunction "1_1") (pintype "passive"))
      (node (ref "C57") (pin "1") (pinfunction "1_1") (pintype "passive"))
      (node (ref "C6") (pin "1") (pinfunction "1_1") (pintype "passive"))
      (node (ref "C7") (pin "1") (pinfunction "1_1") (pintype "passive"))
      (node (ref "C8") (pin "1") (pinfunction "1_1") (pintype "passive"))
      (node (ref "D3") (pin "1") (pinfunction "A_1") (pintype "passive"))
      (node (ref "D5") (pin "K") (pinfunction "K_K") (pintype "passive"))
      (node (ref "Q1") (pin "10") (pinfunction "GND_10") (pintype "passive"))
      (node (ref "Q2") (pin "10") (pinfunction "GND_10") (pintype "passive"))
      (node (ref "Q3") (pin "10") (pinfunction "GND_10") (pintype "passive"))
      (node (ref "Q4") (pin "10") (pinfunction "GND_10") (pintype "passive"))
      (node (ref "R11") (pin "1") (pinfunction "1_1") (pintype "passive"))
      (node (ref "R13") (pin "0") (pinfunction "CIN_0") (pintype "passive"))
      (node (ref "R18") (pin "2") (pinfunction "2_2") (pintype "passive"))
      (node (ref "R19") (pin "1") (pinfunction "1_1") (pintype "passive"))
      (node (ref "R22") (pin "1") (pinfunction "1_1") (pintype "passive"))
      (node (ref "R23") (pin "1") (pinfunction "1_1") (pintype "passive"))
      (node (ref "R26") (pin "1") (pinfunction "1_1") (pintype "passive"))
      (node (ref "R30") (pin "2") (pinfunction "2_2") (pintype "passive"))
      (node (ref "R5") (pin "2") (pinfunction "2_2") (pintype "passive"))
      (node (ref "R8") (pin "2") (pinfunction "2_2") (pintype "passive"))
      (node (ref "R9") (pin "2") (pinfunction "2_2") (pintype "passive"))
      (node (ref "U1") (pin "19") (pinfunction "PGND_19") (pintype "power_in"))
      (node (ref "U1") (pin "26") (pinfunction "ILIM_26") (pintype "passive"))
      (node (ref "U1") (pin "29") (pinfunction "EPAD_29") (pintype "power_in"))
      (node (ref "U1") (pin "5") (pinfunction "SGND_5") (pintype "power_in"))
      (node (ref "U10") (pin "2") (pinfunction "GND_2") (pintype "passive"))
      (node (ref "U11") (pin "2") (pinfunction "GND_2") (pintype "power_in"))
      (node (ref "U2") (pin "2") (pinfunction "GND_2") (pintype "passive"))
      (node (ref "U3") (pin "2") (pinfunction "GND_2") (pintype "power_in"))
      (node (ref "U3") (pin "4") (pinfunction "IN-_4") (pintype "input"))
      (node (ref "U4") (pin "3") (pinfunction "GND_3") (pintype "power_in"))
      (node (ref "U4") (pin "4") (pinfunction "GND_4") (pintype "power_in"))
      (node (ref "U5") (pin "1") (pinfunction "REF_1") (pintype "passive"))
      (node (ref "U5") (pin "2") (pinfunction "GND_2") (pintype "passive"))
      (node (ref "U6") (pin "2") (pinfunction "VSS_2") (pintype "power_in"))
      (node (ref "U7") (pin "3") (pinfunction "GND_3") (pintype "power_in"))
      (node (ref "U7") (pin "4") (pinfunction "GND_4") (pintype "power_in"))
      (node (ref "U8") (pin "21") (pinfunction "GND/EPAD_21") (pintype "power_in"))
      (node (ref "U8") (pin "3") (pinfunction "VSS_3") (pintype "power_in"))
      (node (ref "U9") (pin "2") (pinfunction "GND_2") (pintype "power_in"))
    )
    (net (code "52") (name "MCU5V") (class "Default")
      (node (ref "C39") (pin "2") (pinfunction "2_2") (pintype "passive"))
      (node (ref "C41") (pin "2") (pinfunction "2_2") (pintype "passive"))
      (node (ref "R27") (pin "2") (pinfunction "2_2") (pintype "passive"))
      (node (ref "U10") (pin "5") (pinfunction "VCC_5") (pintype "passive"))
      (node (ref "U7") (pin "5") (pinfunction "VOUT_5") (pintype "power_in"))
      (node (ref "U8") (pin "5") (pinfunction "VDD_5") (pintype "power_in"))
    )
    (net (code "53") (name "Net-(C31-Pad1)") (class "Default")
      (node (ref "C31") (pin "1") (pinfunction "1_1") (pintype "passive"))
      (node (ref "R7") (pin "2") (pinfunction "2_2") (pintype "passive"))
    )
    (net (code "54") (name "Net-(C44-Pad2)") (class "Default")
      (node (ref "C44") (pin "2") (pinfunction "2_2") (pintype "passive"))
      (node (ref "D4") (pin "1") (pinfunction "A_1") (pintype "passive"))
      (node (ref "R24") (pin "2") (pinfunction "2_2") (pintype "passive"))
      (node (ref "R25") (pin "1") (pinfunction "1_1") (pintype "passive"))
    )
    (net (code "55") (name "Net-(D5-PadA)") (class "Default")
      (node (ref "D5") (pin "A") (pinfunction "A_A") (pintype "passive"))
      (node (ref "R31") (pin "1") (pinfunction "1_1") (pintype "passive"))
    )
    (net (code "56") (name "Net-(L1-Pad1)") (class "Default")
      (node (ref "L1") (pin "1") (pinfunction "1_1") (pintype "passive"))
      (node (ref "R1") (pin "1") (pinfunction "CIN_1") (pintype "passive"))
    )
    (net (code "57") (name "Net-(L2-Pad1)") (class "Default")
      (node (ref "L2") (pin "1") (pinfunction "1_1") (pintype "passive"))
      (node (ref "R2") (pin "0") (pinfunction "CIN_0") (pintype "passive"))
    )
    (net (code "58") (name "Net-(U2-BOOT)") (class "Default")
      (node (ref "C5") (pin "2") (pinfunction "2_2") (pintype "passive"))
      (node (ref "U2") (pin "1") (pinfunction "BOOT_1") (pintype "passive"))
    )
    (net (code "59") (name "Net-(U2-LX)") (class "Default")
      (node (ref "C5") (pin "1") (pinfunction "1_1") (pintype "passive"))
      (node (ref "L3") (pin "2") (pinfunction "2_2") (pintype "passive"))
      (node (ref "U2") (pin "6") (pinfunction "LX_6") (pintype "power_in"))
    )
    (net (code "60") (name "Net-(U2-VIN)") (class "Default")
      (node (ref "C6") (pin "2") (pinfunction "2_2") (pintype "passive"))
      (node (ref "R3") (pin "1") (pinfunction "1_1") (pintype "passive"))
      (node (ref "U2") (pin "5") (pinfunction "VIN_5") (pintype "power_in"))
    )
    (net (code "61") (name "Net-(U4-VIN)") (class "Default")
      (node (ref "C35") (pin "2") (pinfunction "2_2") (pintype "passive"))
      (node (ref "FB1") (pin "2") (pinfunction "2_2") (pintype "passive"))
      (node (ref "U4") (pin "1") (pinfunction "VIN_1") (pintype "power_in"))
    )
    (net (code "62") (name "Net-(U6-IN-)") (class "Default")
      (node (ref "C37") (pin "1") (pinfunction "1_1") (pintype "passive"))
      (node (ref "R15") (pin "2") (pinfunction "2_2") (pintype "passive"))
      (node (ref "R16") (pin "1") (pinfunction "1_1") (pintype "passive"))
      (node (ref "U6") (pin "4") (pinfunction "IN-_4") (pintype "input"))
    )
    (net (code "63") (name "Net-(U7-VIN)") (class "Default")
      (node (ref "C40") (pin "2") (pinfunction "2_2") (pintype "passive"))
      (node (ref "FB2") (pin "2") (pinfunction "2_2") (pintype "passive"))
      (node (ref "U7") (pin "1") (pinfunction "VIN_1") (pintype "power_in"))
    )
    (net (code "64") (name "Net-(U9-IN+)") (class "Default")
      (node (ref "C45") (pin "2") (pinfunction "2_2") (pintype "passive"))
      (node (ref "D4") (pin "2") (pinfunction "A_2") (pintype "passive"))
      (node (ref "R25") (pin "2") (pinfunction "2_2") (pintype "passive"))
      (node (ref "U9") (pin "1") (pinfunction "IN+_1") (pintype "input"))
    )
    (net (code "65") (name "Net-(U11-IN+)") (class "Default")
      (node (ref "C56") (pin "2") (pinfunction "2_2") (pintype "passive"))
      (node (ref "R32") (pin "1") (pinfunction "1_1") (pintype "passive"))
      (node (ref "U11") (pin "1") (pinfunction "IN+_1") (pintype "input"))
    )
    (net (code "66") (name "VOUT") (class "Default")
      (node (ref "C16") (pin "2") (pinfunction "2_2") (pintype "passive"))
      (node (ref "C17") (pin "2") (pinfunction "2_2") (pintype "passive"))
      (node (ref "C18") (pin "2") (pinfunction "2_2") (pintype "passive"))
      (node (ref "C19") (pin "2") (pinfunction "2_2") (pintype "passive"))
      (node (ref "C20") (pin "2") (pinfunction "2_2") (pintype "passive"))
      (node (ref "C21") (pin "2") (pinfunction "2_2") (pintype "passive"))
      (node (ref "C22") (pin "2") (pinfunction "2_2") (pintype "passive"))
      (node (ref "C23") (pin "2") (pinfunction "2_2") (pintype "passive"))
      (node (ref "C24") (pin "2") (pinfunction "2_2") (pintype "passive"))
      (node (ref "C3") (pin "1") (pinfunction "1_1") (pintype "passive"))
      (node (ref "C4") (pin "1") (pinfunction "1_1") (pintype "passive"))
      (node (ref "C50") (pin "2") (pinfunction "2_2") (pintype "passive"))
      (node (ref "C51") (pin "2") (pinfunction "2_2") (pintype "passive"))
      (node (ref "C52") (pin "2") (pinfunction "2_2") (pintype "passive"))
      (node (ref "C53") (pin "2") (pinfunction "2_2") (pintype "passive"))
      (node (ref "C54") (pin "2") (pinfunction "2_2") (pintype "passive"))
      (node (ref "Q1") (pin "3") (pinfunction "VDD_3") (pintype "passive"))
      (node (ref "Q1") (pin "4") (pinfunction "VDD_4") (pintype "passive"))
      (node (ref "Q1") (pin "9") (pinfunction "VDD_9") (pintype "passive"))
      (node (ref "Q2") (pin "3") (pinfunction "VDD_3") (pintype "passive"))
      (node (ref "Q2") (pin "4") (pinfunction "VDD_4") (pintype "passive"))
      (node (ref "Q2") (pin "9") (pinfunction "VDD_9") (pintype "passive"))
      (node (ref "Q3") (pin "3") (pinfunction "VDD_3") (pintype "passive"))
      (node (ref "Q3") (pin "4") (pinfunction "VDD_4") (pintype "passive"))
      (node (ref "Q3") (pin "9") (pinfunction "VDD_9") (pintype "passive"))
      (node (ref "Q4") (pin "3") (pinfunction "VDD_3") (pintype "passive"))
      (node (ref "Q4") (pin "4") (pinfunction "VDD_4") (pintype "passive"))
      (node (ref "Q4") (pin "9") (pinfunction "VDD_9") (pintype "passive"))
      (node (ref "R21") (pin "2") (pinfunction "2_2") (pintype "passive"))
      (node (ref "R6") (pin "2") (pinfunction "2_2") (pintype "passive"))
    )
    (net (code "67") (name "unconnected-(U1A-CLKOUT-Pad3)") (class "Default")
      (node (ref "U1") (pin "3") (pinfunction "CLKOUT_3") (pintype "output+no_connect"))
    )
    (net (code "68") (name "unconnected-(U1A-PGOOD-Pad25)") (class "Default")
      (node (ref "U1") (pin "25") (pinfunction "PGOOD_25") (pintype "passive+no_connect"))
    )
    (net (code "69") (name "unconnected-(U1A-PHASMD-Pad2)") (class "Default")
      (node (ref "U1") (pin "2") (pinfunction "PHASMD_2") (pintype "passive+no_connect"))
    )
    (net (code "70") (name "unconnected-(U1E-N{slash}C-Pad12)") (class "Default")
      (node (ref "U1") (pin "12") (pinfunction "N/C_12") (pintype "passive+no_connect"))
    )
    (net (code "71") (name "unconnected-(U4-NC-Pad2)") (class "Default")
      (node (ref "U4") (pin "2") (pinfunction "NC_2") (pintype "passive+no_connect"))
    )
    (net (code "72") (name "unconnected-(U7-NC-Pad2)") (class "Default")
      (node (ref "U7") (pin "2") (pinfunction "NC_2") (pintype "passive+no_connect"))
    )
    (net (code "73") (name "unconnected-(U8D-P2.4{slash}AN10{slash}OP1O{slash}C0P5{slash}C1P5-Pad17)") (class "Default")
      (node (ref "U8") (pin "17") (pinfunction "P2.4/AN10/OP1O/C0P5/C1P5_17") (pintype "bidirectional+no_connect"))
    )
    (net (code "74") (name "unconnected-(U10-IO3-Pad4)") (class "Default")
      (node (ref "U10") (pin "4") (pinfunction "IO3_4") (pintype "passive+no_connect"))
    )
  )
)
